# jack_driver_2.net
KiCad netlist of a schematic drawn in Altium Designer
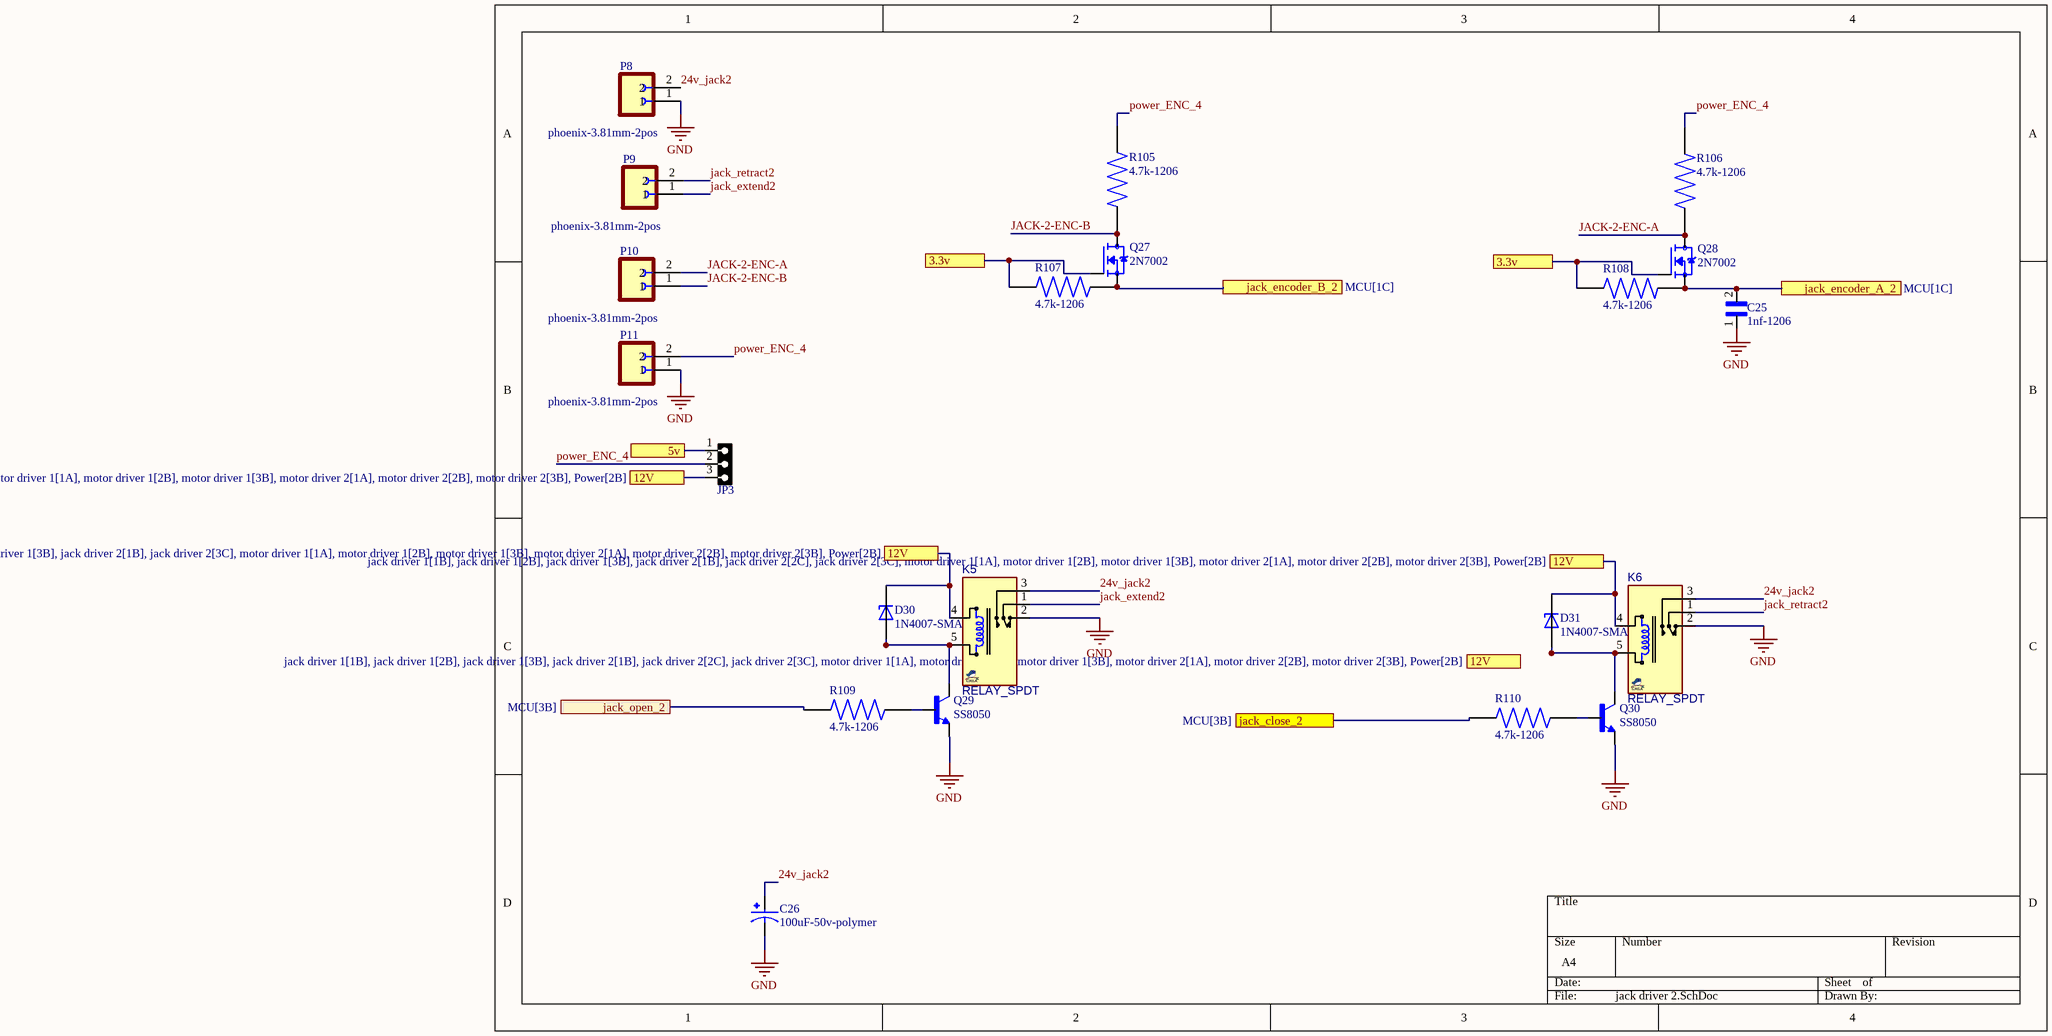
[diagram p0: jack driver 2.SchDoc]

(export (version "E")
  (design (tool "Eeschema 10.0.6"))
  (components
    (comp (ref "C25")
      (value "1nf-1206")
      (footprint "CAPC3216X180N")
      (description "1ÂµF Â±20% 50V Ceramic Capacitor X8R 1206 (3216 Metric)")
      (fields (field (name "MF") "TDK") (field (name "MP") "CGA5L3X8R1H105M160AB"))
      (libsource (lib "cap-1206") (part "CGA5L3X8R1H105M160AB"))
    )
    (comp (ref "C26")
      (value "100uF-50v-polymer")
      (footprint "CAP_EEEFN1H101L")
      (description "CAP ALUM 100UF 20% 50V SMD")
      (fields (field (name "MF") "Panasonic") (field (name "MP") "EEEFN1H101L"))
      (libsource (lib "100uF_50v") (part "EEEFN1H101L"))
    )
    (comp (ref "D30")
      (value "1N4007-SMA")
      (footprint "DIOM4325X250N")
      (description "400W, 30.4V, 5%, Unidirectional, TVS")
      (fields (field (name "MF") "Taiwan Semiconductor") (field (name "MP") "SMAJ26A"))
      (libsource (lib "diode-sma") (part "SMAJ26A"))
    )
    (comp (ref "D31")
      (value "1N4007-SMA")
      (footprint "DIOM4325X250N")
      (description "400W, 30.4V, 5%, Unidirectional, TVS")
      (fields (field (name "MF") "Taiwan Semiconductor") (field (name "MP") "SMAJ26A"))
      (libsource (lib "diode-sma") (part "SMAJ26A"))
    )
    (comp (ref "JP3")
      (value "HDRF3")
      (footprint "HDRLP_F_1X3")
      (description "CONN, HEADER, Male, pitch: 2.54mm, 3POS")
      (libsource (lib "conn_2.54mm_lp") (part "HDRLP_F_1X3"))
    )
    (comp (ref "K5")
      (value "RELAY_SPDT")
      (footprint "REL_SPDT_5_1512")
      (description "Relay, SPDT, 5P, 15.4X12.1mm, 16V/30A")
      (fields (field (name "MANF") "OMRON") (field (name "MANF_P#") "G8QN-1C4 DC12"))
      (libsource (lib "relay") (part "RELAY_SPDT_5_1512_G8QN"))
    )
    (comp (ref "K6")
      (value "RELAY_SPDT")
      (footprint "REL_SPDT_5_1512")
      (description "Relay, SPDT, 5P, 15.4X12.1mm, 16V/30A")
      (fields (field (name "MANF") "OMRON") (field (name "MANF_P#") "G8QN-1C4 DC12"))
      (libsource (lib "relay") (part "RELAY_SPDT_5_1512_G8QN"))
    )
    (comp (ref "P8")
      (value "phoenix-3.81mm-2pos")
      (footprint "PHOENIX_1803578")
      (description "2 Position Terminal Block Plug, Female Sockets 0.150 (3.81mm) 180Â° Free Hanging (In-Line)")
      (fields (field (name "MF") "Phoenix Contact") (field (name "MP") "1803578"))
      (libsource (lib "terminal-phoenix-3.81mm-2pos") (part "1803578"))
    )
    (comp (ref "P9")
      (value "phoenix-3.81mm-2pos")
      (footprint "PHOENIX_1803578")
      (description "2 Position Terminal Block Plug, Female Sockets 0.150 (3.81mm) 180Â° Free Hanging (In-Line)")
      (fields (field (name "MF") "Phoenix Contact") (field (name "MP") "1803578"))
      (libsource (lib "terminal-phoenix-3.81mm-2pos") (part "1803578"))
    )
    (comp (ref "P10")
      (value "phoenix-3.81mm-2pos")
      (footprint "PHOENIX_1803578")
      (description "2 Position Terminal Block Plug, Female Sockets 0.150 (3.81mm) 180Â° Free Hanging (In-Line)")
      (fields (field (name "MF") "Phoenix Contact") (field (name "MP") "1803578"))
      (libsource (lib "terminal-phoenix-3.81mm-2pos") (part "1803578"))
    )
    (comp (ref "P11")
      (value "phoenix-3.81mm-2pos")
      (footprint "PHOENIX_1803578")
      (description "2 Position Terminal Block Plug, Female Sockets 0.150 (3.81mm) 180Â° Free Hanging (In-Line)")
      (fields (field (name "MF") "Phoenix Contact") (field (name "MP") "1803578"))
      (libsource (lib "terminal-phoenix-3.81mm-2pos") (part "1803578"))
    )
    (comp (ref "Q27")
      (value "2N7002")
      (footprint "SOT95P240X111-3N")
      (description "N-Channel 60V 280mA (Ta) 350mW (Ta) Surface Mount SOT-23-3 (TO-236)")
      (fields (field (name "MF") "{'manufacturer': u'onsemi'}"))
      (libsource (lib "2N7002-SOT23") (part "2N7002"))
    )
    (comp (ref "Q28")
      (value "2N7002")
      (footprint "SOT95P240X111-3N")
      (description "N-Channel 60V 280mA (Ta) 350mW (Ta) Surface Mount SOT-23-3 (TO-236)")
      (fields (field (name "MF") "{'manufacturer': u'onsemi'}"))
      (libsource (lib "2N7002-SOT23") (part "2N7002"))
    )
    (comp (ref "Q29")
      (value "SS8050")
      (footprint "TRANS_SS8050-G")
      (description "Bipolar (BJT) Transistor NPN 25 V 1.5 A 100MHz 300 mW Surface Mount SOT-23-3")
      (fields (field (name "DIGI-KEY_PART_NUMBER") "641-1790-2-ND") (field (name "MP") "SS8050G"))
      (libsource (lib "SS8050-G") (part "SS8050-G"))
    )
    (comp (ref "Q30")
      (value "SS8050")
      (footprint "TRANS_SS8050-G")
      (description "Bipolar (BJT) Transistor NPN 25 V 1.5 A 100MHz 300 mW Surface Mount SOT-23-3")
      (fields (field (name "DIGI-KEY_PART_NUMBER") "641-1790-2-ND") (field (name "MP") "SS8050G"))
      (libsource (lib "SS8050-G") (part "SS8050-G"))
    )
    (comp (ref "R105")
      (value "4.7k-1206")
      (footprint "RESC3015X65N")
      (description "Res Thin Film 1206 10K Ohm 0.1% 1/8W Â±25ppm/Â°C Molded SMD SMD Paper T/R")
      (fields (field (name "MF") "TE Connectivity") (field (name "MP") "CPF1206B10KE1"))
      (libsource (lib "resistor-1206") (part "CPF1206B10KE1"))
    )
    (comp (ref "R106")
      (value "4.7k-1206")
      (footprint "RESC3015X65N")
      (description "Res Thin Film 1206 10K Ohm 0.1% 1/8W Â±25ppm/Â°C Molded SMD SMD Paper T/R")
      (fields (field (name "MF") "TE Connectivity") (field (name "MP") "CPF1206B10KE1"))
      (libsource (lib "resistor-1206") (part "CPF1206B10KE1"))
    )
    (comp (ref "R107")
      (value "4.7k-1206")
      (footprint "RESC3015X65N")
      (description "Res Thin Film 1206 10K Ohm 0.1% 1/8W Â±25ppm/Â°C Molded SMD SMD Paper T/R")
      (fields (field (name "MF") "TE Connectivity") (field (name "MP") "CPF1206B10KE1"))
      (libsource (lib "resistor-1206") (part "CPF1206B10KE1"))
    )
    (comp (ref "R108")
      (value "4.7k-1206")
      (footprint "RESC3015X65N")
      (description "Res Thin Film 1206 10K Ohm 0.1% 1/8W Â±25ppm/Â°C Molded SMD SMD Paper T/R")
      (fields (field (name "MF") "TE Connectivity") (field (name "MP") "CPF1206B10KE1"))
      (libsource (lib "resistor-1206") (part "CPF1206B10KE1"))
    )
    (comp (ref "R109")
      (value "4.7k-1206")
      (footprint "RESC3015X65N")
      (description "Res Thin Film 1206 10K Ohm 0.1% 1/8W Â±25ppm/Â°C Molded SMD SMD Paper T/R")
      (fields (field (name "MF") "TE Connectivity") (field (name "MP") "CPF1206B10KE1"))
      (libsource (lib "resistor-1206") (part "CPF1206B10KE1"))
    )
    (comp (ref "R110")
      (value "4.7k-1206")
      (footprint "RESC3015X65N")
      (description "Res Thin Film 1206 10K Ohm 0.1% 1/8W Â±25ppm/Â°C Molded SMD SMD Paper T/R")
      (fields (field (name "MF") "TE Connectivity") (field (name "MP") "CPF1206B10KE1"))
      (libsource (lib "resistor-1206") (part "CPF1206B10KE1"))
    )
  )
  (nets
    (net (code "1") (name "/3.3v") (class "Default")
      (node (ref "Q27") (pin "1") (pinfunction "G_1") (pintype "passive"))
      (node (ref "Q28") (pin "1") (pinfunction "G_1") (pintype "passive"))
      (node (ref "R107") (pin "2") (pinfunction "2_2") (pintype "passive"))
      (node (ref "R108") (pin "2") (pinfunction "2_2") (pintype "passive"))
    )
    (net (code "2") (name "/5v") (class "Default")
      (node (ref "JP3") (pin "1") (pinfunction "1_1") (pintype "passive"))
    )
    (net (code "3") (name "/12V") (class "Default")
      (node (ref "D30") (pin "C") (pinfunction "C_C") (pintype "passive"))
      (node (ref "D31") (pin "C") (pinfunction "C_C") (pintype "passive"))
      (node (ref "JP3") (pin "3") (pinfunction "3_3") (pintype "passive"))
      (node (ref "K5") (pin "4") (pinfunction "T1_4") (pintype "passive"))
      (node (ref "K6") (pin "4") (pinfunction "T1_4") (pintype "passive"))
    )
    (net (code "4") (name "/24v_jack2") (class "Default")
      (node (ref "C26") (pin "1") (pinfunction "1_1") (pintype "passive"))
      (node (ref "K5") (pin "3") (pinfunction "NO_3") (pintype "passive"))
      (node (ref "K6") (pin "3") (pinfunction "NO_3") (pintype "passive"))
      (node (ref "P8") (pin "2") (pinfunction "2_2") (pintype "passive"))
    )
    (net (code "5") (name "/JACK-2-ENC-A") (class "Default")
      (node (ref "P10") (pin "2") (pinfunction "2_2") (pintype "passive"))
      (node (ref "Q28") (pin "3") (pinfunction "D_3") (pintype "passive"))
      (node (ref "R106") (pin "1") (pinfunction "1_1") (pintype "passive"))
    )
    (net (code "6") (name "/JACK-2-ENC-B") (class "Default")
      (node (ref "P10") (pin "1") (pinfunction "1_1") (pintype "passive"))
      (node (ref "Q27") (pin "3") (pinfunction "D_3") (pintype "passive"))
      (node (ref "R105") (pin "1") (pinfunction "1_1") (pintype "passive"))
    )
    (net (code "7") (name "/jack_close_2") (class "Default")
      (node (ref "R110") (pin "2") (pinfunction "2_2") (pintype "passive"))
    )
    (net (code "8") (name "/jack_encoder_A_2") (class "Default")
      (node (ref "C25") (pin "2") (pinfunction "2_2") (pintype "passive"))
      (node (ref "Q28") (pin "2") (pinfunction "S_2") (pintype "passive"))
      (node (ref "R108") (pin "1") (pinfunction "1_1") (pintype "passive"))
    )
    (net (code "9") (name "/jack_encoder_B_2") (class "Default")
      (node (ref "Q27") (pin "2") (pinfunction "S_2") (pintype "passive"))
      (node (ref "R107") (pin "1") (pinfunction "1_1") (pintype "passive"))
    )
    (net (code "10") (name "/jack_extend2") (class "Default")
      (node (ref "K5") (pin "1") (pinfunction "COM_1") (pintype "passive"))
      (node (ref "P9") (pin "1") (pinfunction "1_1") (pintype "passive"))
    )
    (net (code "11") (name "/jack_open_2") (class "Default")
      (node (ref "R109") (pin "2") (pinfunction "2_2") (pintype "passive"))
    )
    (net (code "12") (name "/jack_retract2") (class "Default")
      (node (ref "K6") (pin "1") (pinfunction "COM_1") (pintype "passive"))
      (node (ref "P9") (pin "2") (pinfunction "2_2") (pintype "passive"))
    )
    (net (code "13") (name "/power_ENC_4") (class "Default")
      (node (ref "JP3") (pin "2") (pinfunction "2_2") (pintype "passive"))
      (node (ref "P11") (pin "2") (pinfunction "2_2") (pintype "passive"))
      (node (ref "R105") (pin "2") (pinfunction "2_2") (pintype "passive"))
      (node (ref "R106") (pin "2") (pinfunction "2_2") (pintype "passive"))
    )
    (net (code "14") (name "GND") (class "Default")
      (node (ref "C25") (pin "1") (pinfunction "1_1") (pintype "passive"))
      (node (ref "C26") (pin "2") (pinfunction "2_2") (pintype "passive"))
      (node (ref "K5") (pin "2") (pinfunction "NC_2") (pintype "passive"))
      (node (ref "K6") (pin "2") (pinfunction "NC_2") (pintype "passive"))
      (node (ref "P11") (pin "1") (pinfunction "1_1") (pintype "passive"))
      (node (ref "P8") (pin "1") (pinfunction "1_1") (pintype "passive"))
      (node (ref "Q29") (pin "2") (pinfunction "E_2") (pintype "passive"))
      (node (ref "Q30") (pin "2") (pinfunction "E_2") (pintype "passive"))
    )
    (net (code "15") (name "Net-(K5-T2)") (class "Default")
      (node (ref "D30") (pin "A") (pinfunction "A_A") (pintype "passive"))
      (node (ref "K5") (pin "5") (pinfunction "T2_5") (pintype "passive"))
      (node (ref "Q29") (pin "3") (pinfunction "C_3") (pintype "passive"))
    )
    (net (code "16") (name "Net-(K6-T2)") (class "Default")
      (node (ref "D31") (pin "A") (pinfunction "A_A") (pintype "passive"))
      (node (ref "K6") (pin "5") (pinfunction "T2_5") (pintype "passive"))
      (node (ref "Q30") (pin "3") (pinfunction "C_3") (pintype "passive"))
    )
    (net (code "17") (name "Net-(Q29-B)") (class "Default")
      (node (ref "Q29") (pin "1") (pinfunction "B_1") (pintype "passive"))
      (node (ref "R109") (pin "1") (pinfunction "1_1") (pintype "passive"))
    )
    (net (code "18") (name "Net-(Q30-B)") (class "Default")
      (node (ref "Q30") (pin "1") (pinfunction "B_1") (pintype "passive"))
      (node (ref "R110") (pin "1") (pinfunction "1_1") (pintype "passive"))
    )
  )
)
